# M516A.net
KiCad netlist of a schematic drawn in EAGLE
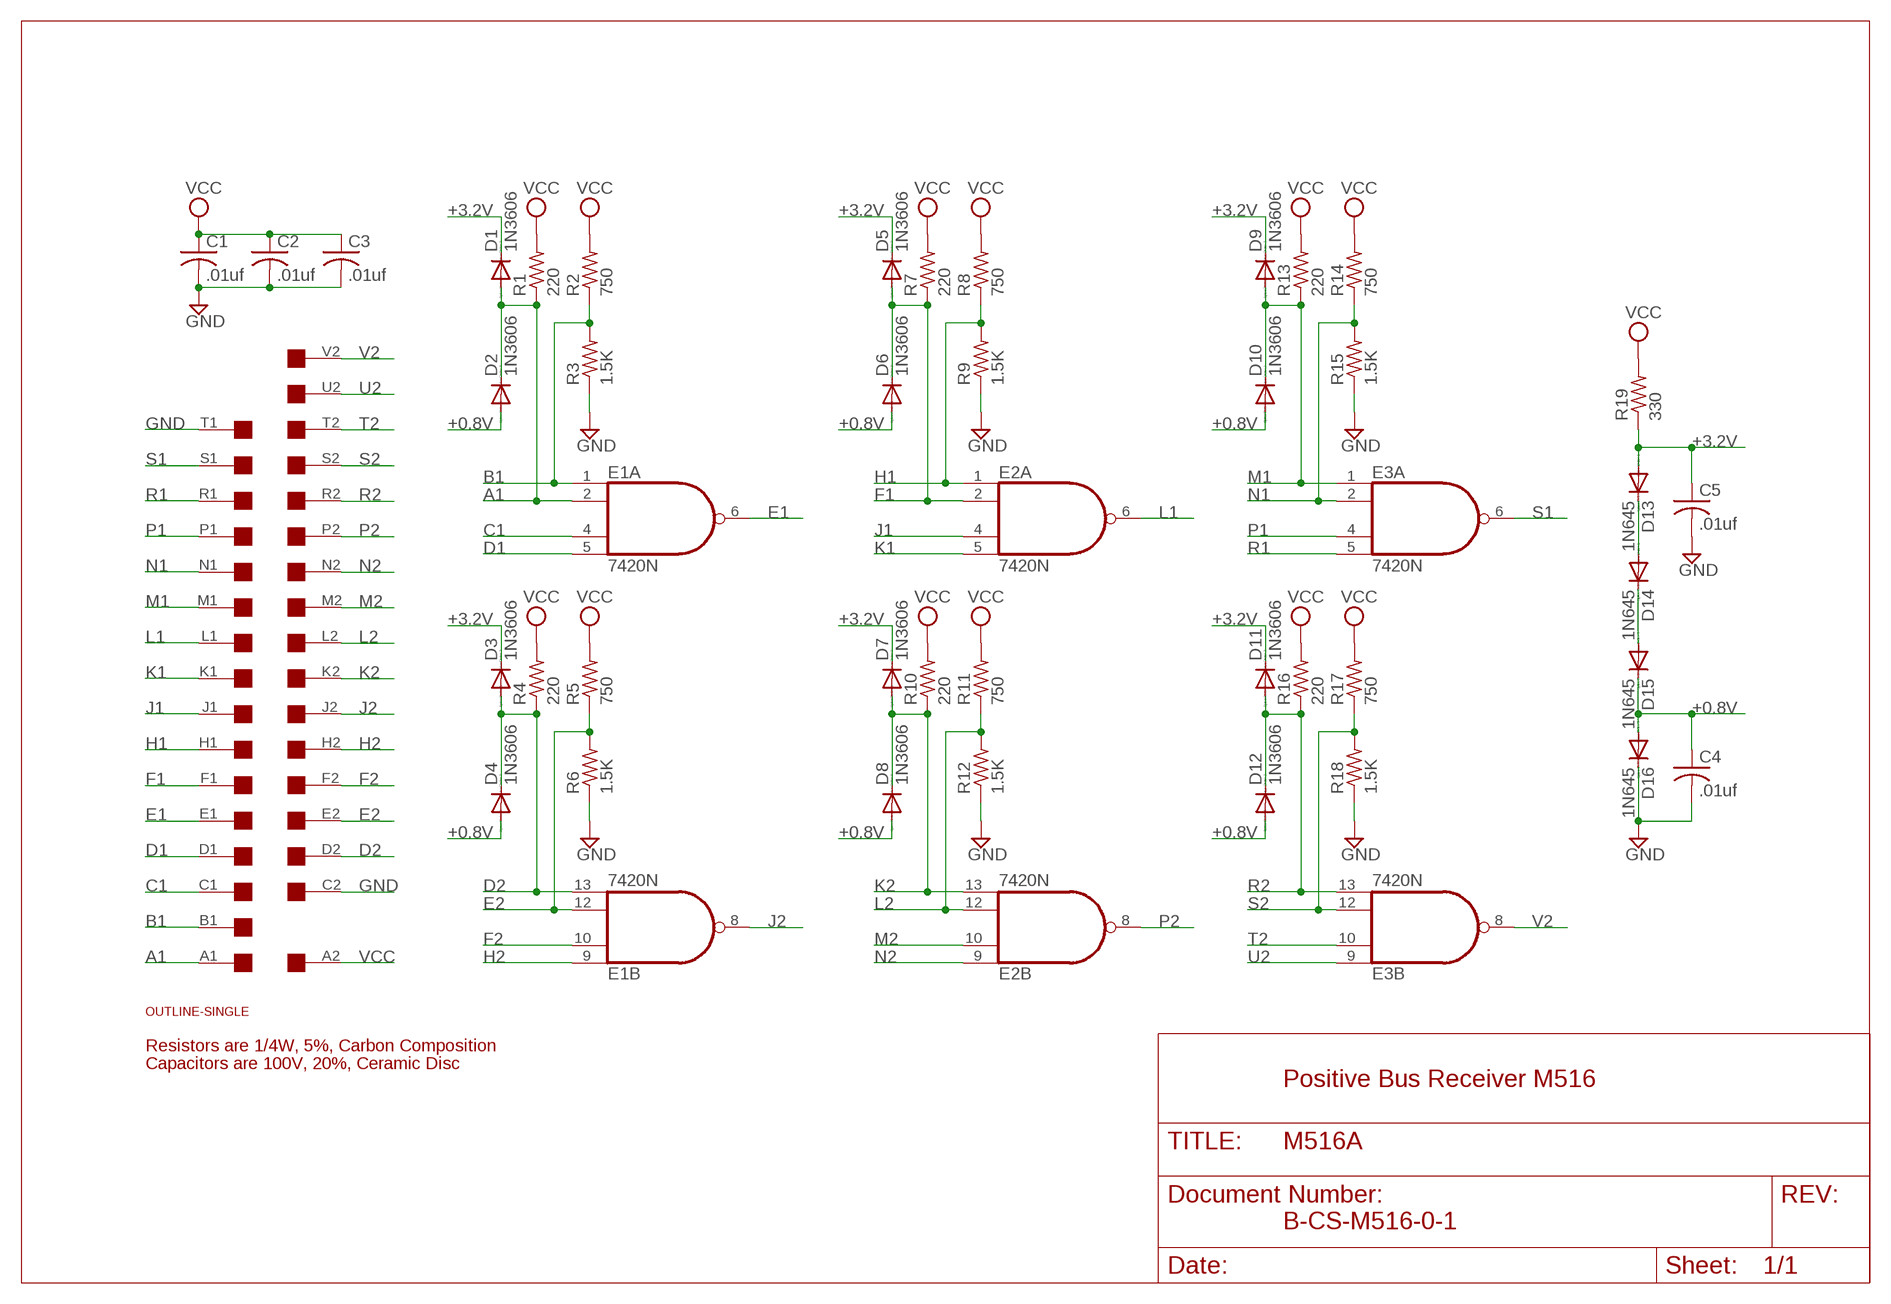
[diagram p0: schematic, sheet 1]

(export (version "E")
  (design (tool "Eeschema 10.0.6"))
  (components
    (comp (ref "C1")
      (value ".01uf")
      (footprint "eagle-import:C050-025X075")
      (libsource (lib "eagle-import") (part "C-US050-025X075"))
    )
    (comp (ref "C2")
      (value ".01uf")
      (footprint "eagle-import:C050-025X075")
      (libsource (lib "eagle-import") (part "C-US050-025X075"))
    )
    (comp (ref "C3")
      (value ".01uf")
      (footprint "eagle-import:C050-025X075")
      (libsource (lib "eagle-import") (part "C-US050-025X075"))
    )
    (comp (ref "C4")
      (value ".01uf")
      (footprint "eagle-import:C050-025X075")
      (libsource (lib "eagle-import") (part "C-US050-025X075"))
    )
    (comp (ref "C5")
      (value ".01uf")
      (footprint "eagle-import:C050-025X075")
      (libsource (lib "eagle-import") (part "C-US050-025X075"))
    )
    (comp (ref "D1")
      (value "1N3606")
      (footprint "eagle-import:DO35-10")
      (libsource (lib "eagle-import") (part "1N4148DO35-10"))
    )
    (comp (ref "D2")
      (value "1N3606")
      (footprint "eagle-import:DO35-10")
      (libsource (lib "eagle-import") (part "1N4148DO35-10"))
    )
    (comp (ref "D3")
      (value "1N3606")
      (footprint "eagle-import:DO35-10")
      (libsource (lib "eagle-import") (part "1N4148DO35-10"))
    )
    (comp (ref "D4")
      (value "1N3606")
      (footprint "eagle-import:DO35-10")
      (libsource (lib "eagle-import") (part "1N4148DO35-10"))
    )
    (comp (ref "D5")
      (value "1N3606")
      (footprint "eagle-import:DO35-10")
      (libsource (lib "eagle-import") (part "1N4148DO35-10"))
    )
    (comp (ref "D6")
      (value "1N3606")
      (footprint "eagle-import:DO35-10")
      (libsource (lib "eagle-import") (part "1N4148DO35-10"))
    )
    (comp (ref "D7")
      (value "1N3606")
      (footprint "eagle-import:DO35-10")
      (libsource (lib "eagle-import") (part "1N4148DO35-10"))
    )
    (comp (ref "D8")
      (value "1N3606")
      (footprint "eagle-import:DO35-10")
      (libsource (lib "eagle-import") (part "1N4148DO35-10"))
    )
    (comp (ref "D9")
      (value "1N3606")
      (footprint "eagle-import:DO35-10")
      (libsource (lib "eagle-import") (part "1N4148DO35-10"))
    )
    (comp (ref "D10")
      (value "1N3606")
      (footprint "eagle-import:DO35-10")
      (libsource (lib "eagle-import") (part "1N4148DO35-10"))
    )
    (comp (ref "D11")
      (value "1N3606")
      (footprint "eagle-import:DO35-10")
      (libsource (lib "eagle-import") (part "1N4148DO35-10"))
    )
    (comp (ref "D12")
      (value "1N3606")
      (footprint "eagle-import:DO35-10")
      (libsource (lib "eagle-import") (part "1N4148DO35-10"))
    )
    (comp (ref "D13")
      (value "1N645")
      (footprint "eagle-import:DO35-10")
      (libsource (lib "eagle-import") (part "1N4148DO35-10"))
    )
    (comp (ref "D14")
      (value "1N645")
      (footprint "eagle-import:DO35-10")
      (libsource (lib "eagle-import") (part "1N4148DO35-10"))
    )
    (comp (ref "D15")
      (value "1N645")
      (footprint "eagle-import:DO35-10")
      (libsource (lib "eagle-import") (part "1N4148DO35-10"))
    )
    (comp (ref "D16")
      (value "1N645")
      (footprint "eagle-import:DO35-10")
      (libsource (lib "eagle-import") (part "1N4148DO35-10"))
    )
    (comp (ref "E1")
      (value "7420N")
      (footprint "eagle-import:DIL14")
      (libsource (lib "eagle-import") (part "7420NS"))
    )
    (comp (ref "E2")
      (value "7420N")
      (footprint "eagle-import:DIL14")
      (libsource (lib "eagle-import") (part "7420NS"))
    )
    (comp (ref "E3")
      (value "7420N")
      (footprint "eagle-import:DIL14")
      (libsource (lib "eagle-import") (part "7420NS"))
    )
    (comp (ref "R1")
      (value "220")
      (footprint "eagle-import:0207_10")
      (libsource (lib "eagle-import") (part "R-US_0207/10"))
    )
    (comp (ref "R2")
      (value "750")
      (footprint "eagle-import:0207_10")
      (libsource (lib "eagle-import") (part "R-US_0207/10"))
    )
    (comp (ref "R3")
      (value "1.5K")
      (footprint "eagle-import:0207_10")
      (libsource (lib "eagle-import") (part "R-US_0207/10"))
    )
    (comp (ref "R4")
      (value "220")
      (footprint "eagle-import:0207_10")
      (libsource (lib "eagle-import") (part "R-US_0207/10"))
    )
    (comp (ref "R5")
      (value "750")
      (footprint "eagle-import:0207_10")
      (libsource (lib "eagle-import") (part "R-US_0207/10"))
    )
    (comp (ref "R6")
      (value "1.5K")
      (footprint "eagle-import:0207_10")
      (libsource (lib "eagle-import") (part "R-US_0207/10"))
    )
    (comp (ref "R7")
      (value "220")
      (footprint "eagle-import:0207_10")
      (libsource (lib "eagle-import") (part "R-US_0207/10"))
    )
    (comp (ref "R8")
      (value "750")
      (footprint "eagle-import:0207_10")
      (libsource (lib "eagle-import") (part "R-US_0207/10"))
    )
    (comp (ref "R9")
      (value "1.5K")
      (footprint "eagle-import:0207_10")
      (libsource (lib "eagle-import") (part "R-US_0207/10"))
    )
    (comp (ref "R10")
      (value "220")
      (footprint "eagle-import:0207_10")
      (libsource (lib "eagle-import") (part "R-US_0207/10"))
    )
    (comp (ref "R11")
      (value "750")
      (footprint "eagle-import:0207_10")
      (libsource (lib "eagle-import") (part "R-US_0207/10"))
    )
    (comp (ref "R12")
      (value "1.5K")
      (footprint "eagle-import:0207_10")
      (libsource (lib "eagle-import") (part "R-US_0207/10"))
    )
    (comp (ref "R13")
      (value "220")
      (footprint "eagle-import:0207_10")
      (libsource (lib "eagle-import") (part "R-US_0207/10"))
    )
    (comp (ref "R14")
      (value "750")
      (footprint "eagle-import:0207_10")
      (libsource (lib "eagle-import") (part "R-US_0207/10"))
    )
    (comp (ref "R15")
      (value "1.5K")
      (footprint "eagle-import:0207_10")
      (libsource (lib "eagle-import") (part "R-US_0207/10"))
    )
    (comp (ref "R16")
      (value "220")
      (footprint "eagle-import:0207_10")
      (libsource (lib "eagle-import") (part "R-US_0207/10"))
    )
    (comp (ref "R17")
      (value "750")
      (footprint "eagle-import:0207_10")
      (libsource (lib "eagle-import") (part "R-US_0207/10"))
    )
    (comp (ref "R18")
      (value "1.5K")
      (footprint "eagle-import:0207_10")
      (libsource (lib "eagle-import") (part "R-US_0207/10"))
    )
    (comp (ref "R19")
      (value "330")
      (footprint "eagle-import:0207_10")
      (libsource (lib "eagle-import") (part "R-US_0207/10"))
    )
    (comp (ref "U$1")
      (value "OUTLINE-SINGLE")
      (footprint "eagle-import:SINGLE")
      (libsource (lib "eagle-import") (part "OUTLINE-SINGLE"))
    )
    (comp (ref "U$2")
      (value "SINGLE")
      (footprint "eagle-import:EDGE-CON2")
      (libsource (lib "eagle-import") (part "SINGLE"))
    )
  )
  (nets
    (net (code "1") (name "/+0.8V") (class "Default")
      (node (ref "C4") (pin "1") (pinfunction "1_1") (pintype "passive"))
      (node (ref "D10") (pin "A") (pinfunction "A_A") (pintype "passive"))
      (node (ref "D12") (pin "A") (pinfunction "A_A") (pintype "passive"))
      (node (ref "D15") (pin "C") (pinfunction "C_C") (pintype "passive"))
      (node (ref "D16") (pin "A") (pinfunction "A_A") (pintype "passive"))
      (node (ref "D2") (pin "A") (pinfunction "A_A") (pintype "passive"))
      (node (ref "D4") (pin "A") (pinfunction "A_A") (pintype "passive"))
      (node (ref "D6") (pin "A") (pinfunction "A_A") (pintype "passive"))
      (node (ref "D8") (pin "A") (pinfunction "A_A") (pintype "passive"))
    )
    (net (code "2") (name "/+3.2V") (class "Default")
      (node (ref "C5") (pin "1") (pinfunction "1_1") (pintype "passive"))
      (node (ref "D1") (pin "C") (pinfunction "C_C") (pintype "passive"))
      (node (ref "D11") (pin "C") (pinfunction "C_C") (pintype "passive"))
      (node (ref "D13") (pin "A") (pinfunction "A_A") (pintype "passive"))
      (node (ref "D3") (pin "C") (pinfunction "C_C") (pintype "passive"))
      (node (ref "D5") (pin "C") (pinfunction "C_C") (pintype "passive"))
      (node (ref "D7") (pin "C") (pinfunction "C_C") (pintype "passive"))
      (node (ref "D9") (pin "C") (pinfunction "C_C") (pintype "passive"))
      (node (ref "R19") (pin "1") (pinfunction "1_1") (pintype "passive"))
    )
    (net (code "3") (name "/A1") (class "Default")
      (node (ref "D1") (pin "A") (pinfunction "A_A") (pintype "passive"))
      (node (ref "D2") (pin "C") (pinfunction "C_C") (pintype "passive"))
      (node (ref "E1") (pin "2") (pinfunction "I1_2") (pintype "input"))
      (node (ref "R1") (pin "1") (pinfunction "1_1") (pintype "passive"))
      (node (ref "U$2") (pin "A1") (pinfunction "1_A1") (pintype "bidirectional"))
    )
    (net (code "4") (name "/B1") (class "Default")
      (node (ref "E1") (pin "1") (pinfunction "I0_1") (pintype "input"))
      (node (ref "R2") (pin "1") (pinfunction "1_1") (pintype "passive"))
      (node (ref "R3") (pin "2") (pinfunction "2_2") (pintype "passive"))
      (node (ref "U$2") (pin "B1") (pinfunction "1_B1") (pintype "bidirectional"))
    )
    (net (code "5") (name "/C1") (class "Default")
      (node (ref "E1") (pin "4") (pinfunction "I2_4") (pintype "input"))
      (node (ref "U$2") (pin "C1") (pinfunction "1_C1") (pintype "bidirectional"))
    )
    (net (code "6") (name "/D1") (class "Default")
      (node (ref "E1") (pin "5") (pinfunction "I3_5") (pintype "input"))
      (node (ref "U$2") (pin "D1") (pinfunction "1_D1") (pintype "bidirectional"))
    )
    (net (code "7") (name "/D2") (class "Default")
      (node (ref "D3") (pin "A") (pinfunction "A_A") (pintype "passive"))
      (node (ref "D4") (pin "C") (pinfunction "C_C") (pintype "passive"))
      (node (ref "E1") (pin "13") (pinfunction "I3_13") (pintype "input"))
      (node (ref "R4") (pin "1") (pinfunction "1_1") (pintype "passive"))
      (node (ref "U$2") (pin "D2") (pinfunction "1_D2") (pintype "bidirectional"))
    )
    (net (code "8") (name "/E1") (class "Default")
      (node (ref "E1") (pin "6") (pinfunction "O_6") (pintype "output"))
      (node (ref "U$2") (pin "E1") (pinfunction "1_E1") (pintype "bidirectional"))
    )
    (net (code "9") (name "/E2") (class "Default")
      (node (ref "E1") (pin "12") (pinfunction "I2_12") (pintype "input"))
      (node (ref "R5") (pin "1") (pinfunction "1_1") (pintype "passive"))
      (node (ref "R6") (pin "2") (pinfunction "2_2") (pintype "passive"))
      (node (ref "U$2") (pin "E2") (pinfunction "1_E2") (pintype "bidirectional"))
    )
    (net (code "10") (name "/F1") (class "Default")
      (node (ref "D5") (pin "A") (pinfunction "A_A") (pintype "passive"))
      (node (ref "D6") (pin "C") (pinfunction "C_C") (pintype "passive"))
      (node (ref "E2") (pin "2") (pinfunction "I1_2") (pintype "input"))
      (node (ref "R7") (pin "1") (pinfunction "1_1") (pintype "passive"))
      (node (ref "U$2") (pin "F1") (pinfunction "1_F1") (pintype "bidirectional"))
    )
    (net (code "11") (name "/F2") (class "Default")
      (node (ref "E1") (pin "10") (pinfunction "I1_10") (pintype "input"))
      (node (ref "U$2") (pin "F2") (pinfunction "1_F2") (pintype "bidirectional"))
    )
    (net (code "12") (name "/H1") (class "Default")
      (node (ref "E2") (pin "1") (pinfunction "I0_1") (pintype "input"))
      (node (ref "R8") (pin "1") (pinfunction "1_1") (pintype "passive"))
      (node (ref "R9") (pin "2") (pinfunction "2_2") (pintype "passive"))
      (node (ref "U$2") (pin "H1") (pinfunction "1_H1") (pintype "bidirectional"))
    )
    (net (code "13") (name "/H2") (class "Default")
      (node (ref "E1") (pin "9") (pinfunction "I0_9") (pintype "input"))
      (node (ref "U$2") (pin "H2") (pinfunction "1_H2") (pintype "bidirectional"))
    )
    (net (code "14") (name "/J1") (class "Default")
      (node (ref "E2") (pin "4") (pinfunction "I2_4") (pintype "input"))
      (node (ref "U$2") (pin "J1") (pinfunction "1_J1") (pintype "bidirectional"))
    )
    (net (code "15") (name "/J2") (class "Default")
      (node (ref "E1") (pin "8") (pinfunction "O_8") (pintype "output"))
      (node (ref "U$2") (pin "J2") (pinfunction "1_J2") (pintype "bidirectional"))
    )
    (net (code "16") (name "/K1") (class "Default")
      (node (ref "E2") (pin "5") (pinfunction "I3_5") (pintype "input"))
      (node (ref "U$2") (pin "K1") (pinfunction "1_K1") (pintype "bidirectional"))
    )
    (net (code "17") (name "/K2") (class "Default")
      (node (ref "D7") (pin "A") (pinfunction "A_A") (pintype "passive"))
      (node (ref "D8") (pin "C") (pinfunction "C_C") (pintype "passive"))
      (node (ref "E2") (pin "13") (pinfunction "I3_13") (pintype "input"))
      (node (ref "R10") (pin "1") (pinfunction "1_1") (pintype "passive"))
      (node (ref "U$2") (pin "K2") (pinfunction "1_K2") (pintype "bidirectional"))
    )
    (net (code "18") (name "/L1") (class "Default")
      (node (ref "E2") (pin "6") (pinfunction "O_6") (pintype "output"))
      (node (ref "U$2") (pin "L1") (pinfunction "1_L1") (pintype "bidirectional"))
    )
    (net (code "19") (name "/L2") (class "Default")
      (node (ref "E2") (pin "12") (pinfunction "I2_12") (pintype "input"))
      (node (ref "R11") (pin "1") (pinfunction "1_1") (pintype "passive"))
      (node (ref "R12") (pin "2") (pinfunction "2_2") (pintype "passive"))
      (node (ref "U$2") (pin "L2") (pinfunction "1_L2") (pintype "bidirectional"))
    )
    (net (code "20") (name "/M1") (class "Default")
      (node (ref "D10") (pin "C") (pinfunction "C_C") (pintype "passive"))
      (node (ref "D9") (pin "A") (pinfunction "A_A") (pintype "passive"))
      (node (ref "E3") (pin "1") (pinfunction "I0_1") (pintype "input"))
      (node (ref "R13") (pin "1") (pinfunction "1_1") (pintype "passive"))
      (node (ref "U$2") (pin "M1") (pinfunction "1_M1") (pintype "bidirectional"))
    )
    (net (code "21") (name "/M2") (class "Default")
      (node (ref "E2") (pin "10") (pinfunction "I1_10") (pintype "input"))
      (node (ref "U$2") (pin "M2") (pinfunction "1_M2") (pintype "bidirectional"))
    )
    (net (code "22") (name "/N1") (class "Default")
      (node (ref "E3") (pin "2") (pinfunction "I1_2") (pintype "input"))
      (node (ref "R14") (pin "1") (pinfunction "1_1") (pintype "passive"))
      (node (ref "R15") (pin "2") (pinfunction "2_2") (pintype "passive"))
      (node (ref "U$2") (pin "N1") (pinfunction "1_N1") (pintype "bidirectional"))
    )
    (net (code "23") (name "/N2") (class "Default")
      (node (ref "E2") (pin "9") (pinfunction "I0_9") (pintype "input"))
      (node (ref "U$2") (pin "N2") (pinfunction "1_N2") (pintype "bidirectional"))
    )
    (net (code "24") (name "/P1") (class "Default")
      (node (ref "E3") (pin "4") (pinfunction "I2_4") (pintype "input"))
      (node (ref "U$2") (pin "P1") (pinfunction "1_P1") (pintype "bidirectional"))
    )
    (net (code "25") (name "/P2") (class "Default")
      (node (ref "E2") (pin "8") (pinfunction "O_8") (pintype "output"))
      (node (ref "U$2") (pin "P2") (pinfunction "1_P2") (pintype "bidirectional"))
    )
    (net (code "26") (name "/R1") (class "Default")
      (node (ref "E3") (pin "5") (pinfunction "I3_5") (pintype "input"))
      (node (ref "U$2") (pin "R1") (pinfunction "1_R1") (pintype "bidirectional"))
    )
    (net (code "27") (name "/R2") (class "Default")
      (node (ref "D11") (pin "A") (pinfunction "A_A") (pintype "passive"))
      (node (ref "D12") (pin "C") (pinfunction "C_C") (pintype "passive"))
      (node (ref "E3") (pin "13") (pinfunction "I3_13") (pintype "input"))
      (node (ref "R16") (pin "1") (pinfunction "1_1") (pintype "passive"))
      (node (ref "U$2") (pin "R2") (pinfunction "1_R2") (pintype "bidirectional"))
    )
    (net (code "28") (name "/S1") (class "Default")
      (node (ref "E3") (pin "6") (pinfunction "O_6") (pintype "output"))
      (node (ref "U$2") (pin "S1") (pinfunction "1_S1") (pintype "bidirectional"))
    )
    (net (code "29") (name "/S2") (class "Default")
      (node (ref "E3") (pin "12") (pinfunction "I2_12") (pintype "input"))
      (node (ref "R17") (pin "1") (pinfunction "1_1") (pintype "passive"))
      (node (ref "R18") (pin "2") (pinfunction "2_2") (pintype "passive"))
      (node (ref "U$2") (pin "S2") (pinfunction "1_S2") (pintype "bidirectional"))
    )
    (net (code "30") (name "/T2") (class "Default")
      (node (ref "E3") (pin "10") (pinfunction "I1_10") (pintype "input"))
      (node (ref "U$2") (pin "T2") (pinfunction "1_T2") (pintype "bidirectional"))
    )
    (net (code "31") (name "/U2") (class "Default")
      (node (ref "E3") (pin "9") (pinfunction "I0_9") (pintype "input"))
      (node (ref "U$2") (pin "U2") (pinfunction "1_U2") (pintype "bidirectional"))
    )
    (net (code "32") (name "/V2") (class "Default")
      (node (ref "E3") (pin "8") (pinfunction "O_8") (pintype "output"))
      (node (ref "U$2") (pin "V2") (pinfunction "1_V2") (pintype "bidirectional"))
    )
    (net (code "33") (name "GND") (class "Default")
      (node (ref "C1") (pin "2") (pinfunction "2_2") (pintype "passive"))
      (node (ref "C2") (pin "2") (pinfunction "2_2") (pintype "passive"))
      (node (ref "C3") (pin "2") (pinfunction "2_2") (pintype "passive"))
      (node (ref "C4") (pin "2") (pinfunction "2_2") (pintype "passive"))
      (node (ref "C5") (pin "2") (pinfunction "2_2") (pintype "passive"))
      (node (ref "D16") (pin "C") (pinfunction "C_C") (pintype "passive"))
      (node (ref "R12") (pin "1") (pinfunction "1_1") (pintype "passive"))
      (node (ref "R15") (pin "1") (pinfunction "1_1") (pintype "passive"))
      (node (ref "R18") (pin "1") (pinfunction "1_1") (pintype "passive"))
      (node (ref "R3") (pin "1") (pinfunction "1_1") (pintype "passive"))
      (node (ref "R6") (pin "1") (pinfunction "1_1") (pintype "passive"))
      (node (ref "R9") (pin "1") (pinfunction "1_1") (pintype "passive"))
      (node (ref "U$2") (pin "C2") (pinfunction "1_C2") (pintype "bidirectional"))
      (node (ref "U$2") (pin "T1") (pinfunction "1_T1") (pintype "bidirectional"))
    )
    (net (code "34") (name "Net-(D13-PadC)") (class "Default")
      (node (ref "D13") (pin "C") (pinfunction "C_C") (pintype "passive"))
      (node (ref "D14") (pin "A") (pinfunction "A_A") (pintype "passive"))
    )
    (net (code "35") (name "Net-(D14-PadC)") (class "Default")
      (node (ref "D14") (pin "C") (pinfunction "C_C") (pintype "passive"))
      (node (ref "D15") (pin "A") (pinfunction "A_A") (pintype "passive"))
    )
    (net (code "36") (name "VCC") (class "Default")
      (node (ref "C1") (pin "1") (pinfunction "1_1") (pintype "passive"))
      (node (ref "C2") (pin "1") (pinfunction "1_1") (pintype "passive"))
      (node (ref "C3") (pin "1") (pinfunction "1_1") (pintype "passive"))
      (node (ref "R1") (pin "2") (pinfunction "2_2") (pintype "passive"))
      (node (ref "R10") (pin "2") (pinfunction "2_2") (pintype "passive"))
      (node (ref "R11") (pin "2") (pinfunction "2_2") (pintype "passive"))
      (node (ref "R13") (pin "2") (pinfunction "2_2") (pintype "passive"))
      (node (ref "R14") (pin "2") (pinfunction "2_2") (pintype "passive"))
      (node (ref "R16") (pin "2") (pinfunction "2_2") (pintype "passive"))
      (node (ref "R17") (pin "2") (pinfunction "2_2") (pintype "passive"))
      (node (ref "R19") (pin "2") (pinfunction "2_2") (pintype "passive"))
      (node (ref "R2") (pin "2") (pinfunction "2_2") (pintype "passive"))
      (node (ref "R4") (pin "2") (pinfunction "2_2") (pintype "passive"))
      (node (ref "R5") (pin "2") (pinfunction "2_2") (pintype "passive"))
      (node (ref "R7") (pin "2") (pinfunction "2_2") (pintype "passive"))
      (node (ref "R8") (pin "2") (pinfunction "2_2") (pintype "passive"))
      (node (ref "U$2") (pin "A2") (pinfunction "1_A2") (pintype "bidirectional"))
    )
  )
)
